# untitled.net
KiCad netlist of a schematic drawn in EAGLE
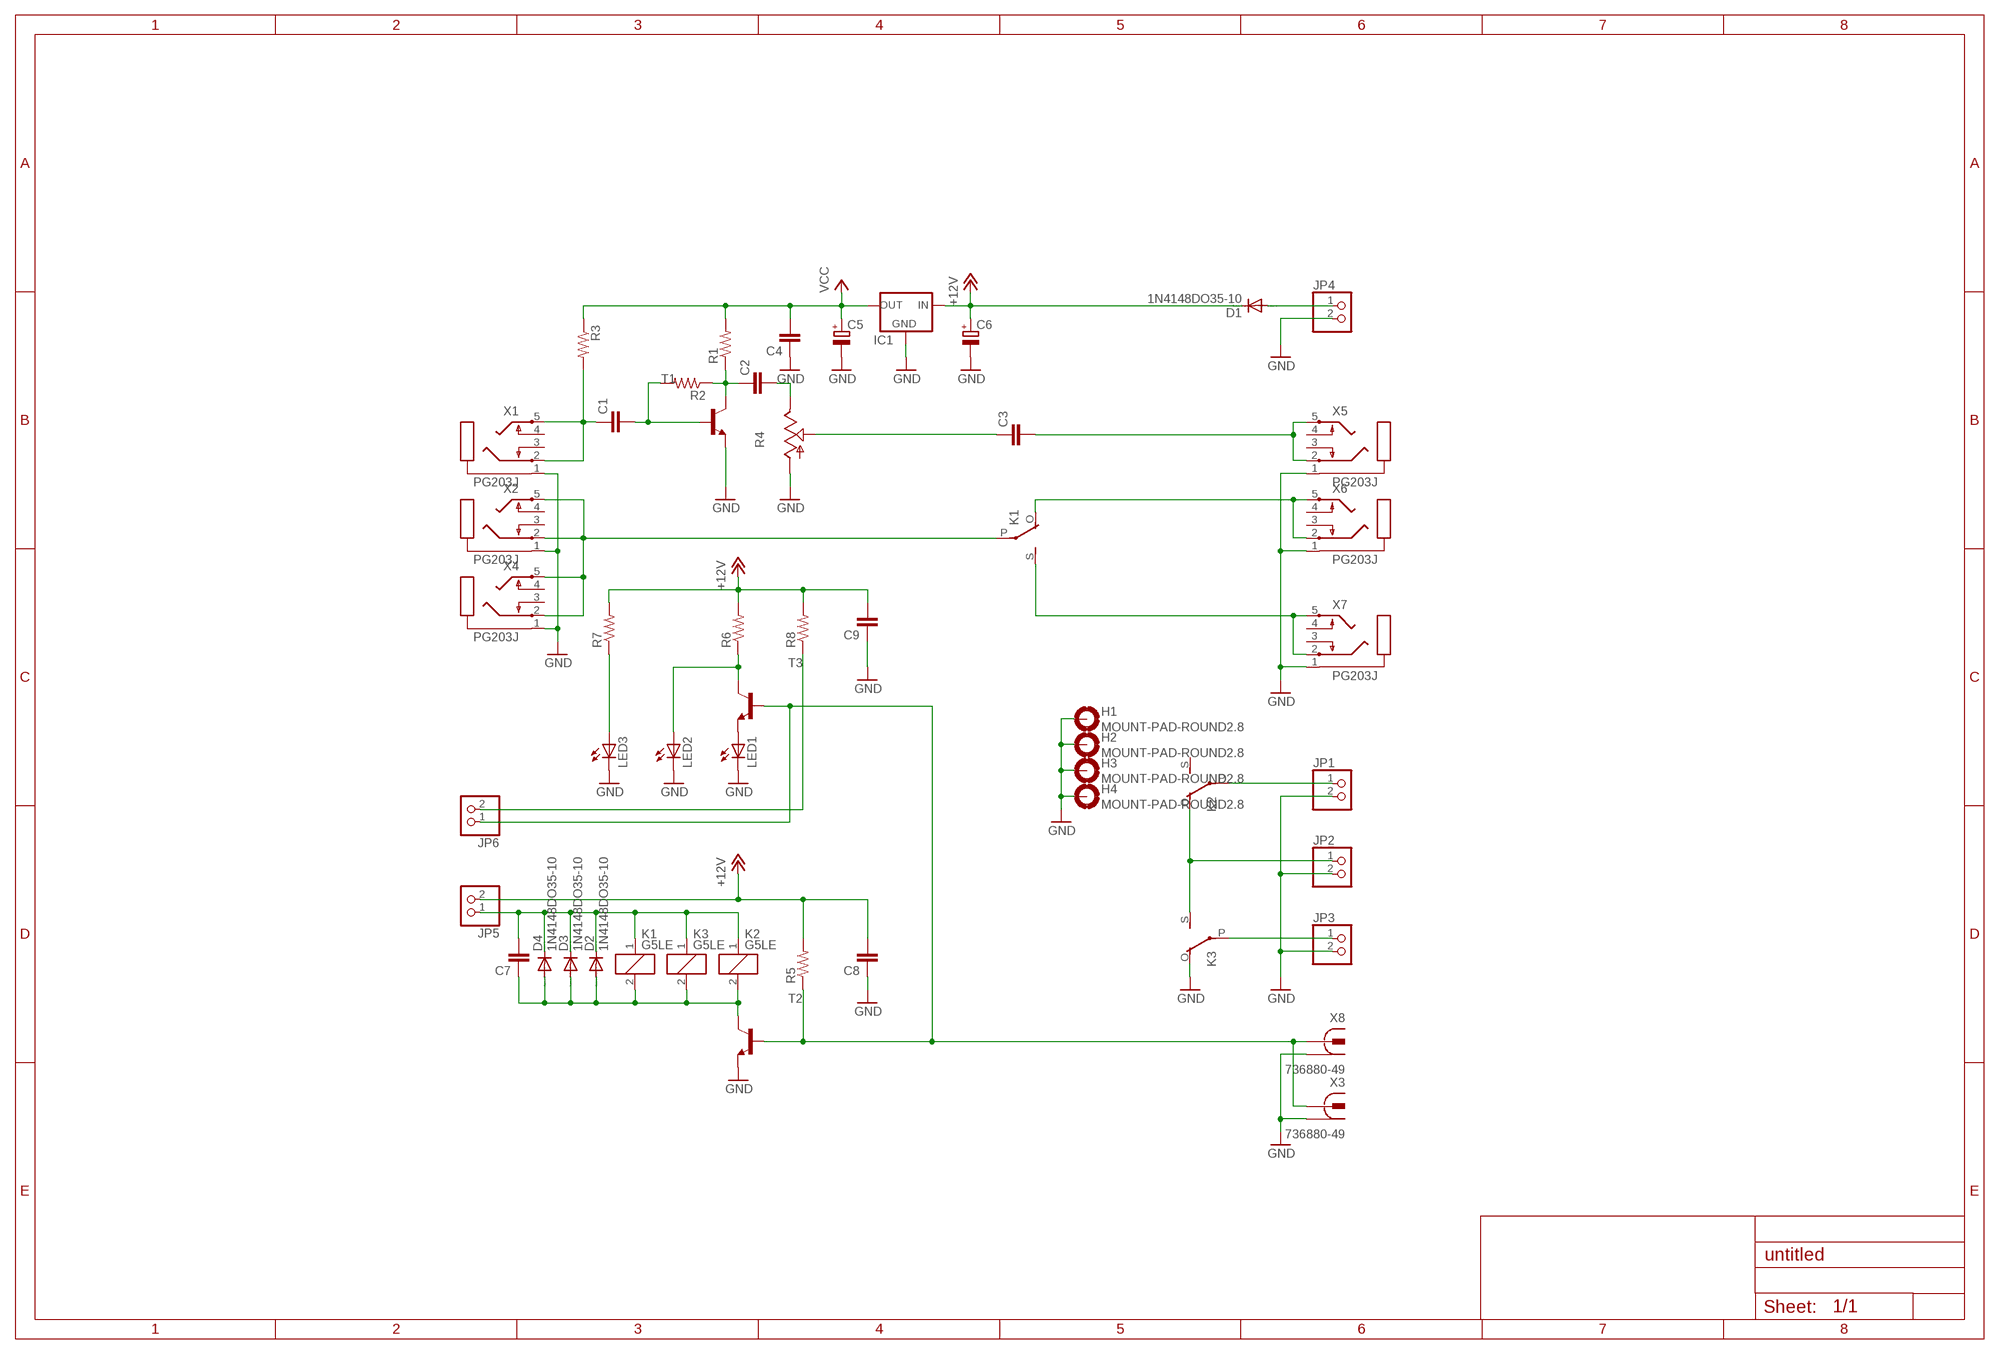
[diagram p0: schematic, sheet 1]

(export (version "E")
  (design (tool "Eeschema 10.0.6"))
  (components
    (comp (ref "C1")
      (value "C-EU050-025X075")
      (footprint "eagle-import:C050-025X075")
      (libsource (lib "eagle-import") (part "C-EU050-025X075"))
    )
    (comp (ref "C2")
      (value "C-EU050-025X075")
      (footprint "eagle-import:C050-025X075")
      (libsource (lib "eagle-import") (part "C-EU050-025X075"))
    )
    (comp (ref "C3")
      (value "C-EU050-025X075")
      (footprint "eagle-import:C050-025X075")
      (libsource (lib "eagle-import") (part "C-EU050-025X075"))
    )
    (comp (ref "C4")
      (value "C-EU050-025X075")
      (footprint "eagle-import:C050-025X075")
      (libsource (lib "eagle-import") (part "C-EU050-025X075"))
    )
    (comp (ref "C5")
      (value "CPOL-EUE2.5-6")
      (footprint "eagle-import:E2,5-6")
      (libsource (lib "eagle-import") (part "CPOL-EUE2.5-6"))
    )
    (comp (ref "C6")
      (value "CPOL-EUE2.5-6")
      (footprint "eagle-import:E2,5-6")
      (libsource (lib "eagle-import") (part "CPOL-EUE2.5-6"))
    )
    (comp (ref "C7")
      (value "C-EU050-025X075")
      (footprint "eagle-import:C050-025X075")
      (libsource (lib "eagle-import") (part "C-EU050-025X075"))
    )
    (comp (ref "C8")
      (value "C-EU050-025X075")
      (footprint "eagle-import:C050-025X075")
      (libsource (lib "eagle-import") (part "C-EU050-025X075"))
    )
    (comp (ref "C9")
      (value "C-EU050-025X075")
      (footprint "eagle-import:C050-025X075")
      (libsource (lib "eagle-import") (part "C-EU050-025X075"))
    )
    (comp (ref "D1")
      (value "1N4148DO35-10")
      (footprint "eagle-import:DO35-10")
      (libsource (lib "eagle-import") (part "1N4148DO35-10"))
    )
    (comp (ref "D2")
      (value "1N4148DO35-10")
      (footprint "eagle-import:DO35-10")
      (libsource (lib "eagle-import") (part "1N4148DO35-10"))
    )
    (comp (ref "D3")
      (value "1N4148DO35-10")
      (footprint "eagle-import:DO35-10")
      (libsource (lib "eagle-import") (part "1N4148DO35-10"))
    )
    (comp (ref "D4")
      (value "1N4148DO35-10")
      (footprint "eagle-import:DO35-10")
      (libsource (lib "eagle-import") (part "1N4148DO35-10"))
    )
    (comp (ref "H1")
      (value "MOUNT-PAD-ROUND2.8")
      (footprint "eagle-import:2,8-PAD")
      (libsource (lib "eagle-import") (part "MOUNT-PAD-ROUND2.8"))
    )
    (comp (ref "H2")
      (value "MOUNT-PAD-ROUND2.8")
      (footprint "eagle-import:2,8-PAD")
      (libsource (lib "eagle-import") (part "MOUNT-PAD-ROUND2.8"))
    )
    (comp (ref "H3")
      (value "MOUNT-PAD-ROUND2.8")
      (footprint "eagle-import:2,8-PAD")
      (libsource (lib "eagle-import") (part "MOUNT-PAD-ROUND2.8"))
    )
    (comp (ref "H4")
      (value "MOUNT-PAD-ROUND2.8")
      (footprint "eagle-import:2,8-PAD")
      (libsource (lib "eagle-import") (part "MOUNT-PAD-ROUND2.8"))
    )
    (comp (ref "IC1")
      (value "78XXS")
      (footprint "eagle-import:78XXS")
      (libsource (lib "eagle-import") (part "78XXS"))
    )
    (comp (ref "JP1")
      (value "PINHD-1X2")
      (footprint "eagle-import:1X02")
      (libsource (lib "eagle-import") (part "PINHD-1X2"))
    )
    (comp (ref "JP2")
      (value "PINHD-1X2")
      (footprint "eagle-import:1X02")
      (libsource (lib "eagle-import") (part "PINHD-1X2"))
    )
    (comp (ref "JP3")
      (value "PINHD-1X2")
      (footprint "eagle-import:1X02")
      (libsource (lib "eagle-import") (part "PINHD-1X2"))
    )
    (comp (ref "JP4")
      (value "PINHD-1X2")
      (footprint "eagle-import:1X02")
      (libsource (lib "eagle-import") (part "PINHD-1X2"))
    )
    (comp (ref "JP5")
      (value "PINHD-1X2")
      (footprint "eagle-import:1X02")
      (libsource (lib "eagle-import") (part "PINHD-1X2"))
    )
    (comp (ref "JP6")
      (value "PINHD-1X2")
      (footprint "eagle-import:1X02")
      (libsource (lib "eagle-import") (part "PINHD-1X2"))
    )
    (comp (ref "K1")
      (value "G5LE")
      (footprint "eagle-import:G5LE")
      (libsource (lib "eagle-import") (part "G5LE"))
    )
    (comp (ref "K2")
      (value "G5LE")
      (footprint "eagle-import:G5LE")
      (libsource (lib "eagle-import") (part "G5LE"))
    )
    (comp (ref "K3")
      (value "G5LE")
      (footprint "eagle-import:G5LE")
      (libsource (lib "eagle-import") (part "G5LE"))
    )
    (comp (ref "LED1")
      (value "LED3MM")
      (footprint "eagle-import:LED3MM")
      (libsource (lib "eagle-import") (part "LED3MM"))
    )
    (comp (ref "LED2")
      (value "LED3MM")
      (footprint "eagle-import:LED3MM")
      (libsource (lib "eagle-import") (part "LED3MM"))
    )
    (comp (ref "LED3")
      (value "LED3MM")
      (footprint "eagle-import:LED3MM")
      (libsource (lib "eagle-import") (part "LED3MM"))
    )
    (comp (ref "R1")
      (value "R-US_0207/7")
      (footprint "eagle-import:0207_7")
      (libsource (lib "eagle-import") (part "R-US_0207/7"))
    )
    (comp (ref "R2")
      (value "R-US_0207/7")
      (footprint "eagle-import:0207_7")
      (libsource (lib "eagle-import") (part "R-US_0207/7"))
    )
    (comp (ref "R3")
      (value "R-US_0207/7")
      (footprint "eagle-import:0207_7")
      (libsource (lib "eagle-import") (part "R-US_0207/7"))
    )
    (comp (ref "R4")
      (value "TRIM_US-CIP20C-6MM")
      (footprint "eagle-import:CIP20C-6MM")
      (libsource (lib "eagle-import") (part "TRIM_US-CIP20C-6MM"))
    )
    (comp (ref "R5")
      (value "R-US_0207/7")
      (footprint "eagle-import:0207_7")
      (libsource (lib "eagle-import") (part "R-US_0207/7"))
    )
    (comp (ref "R6")
      (value "R-US_0207/7")
      (footprint "eagle-import:0207_7")
      (libsource (lib "eagle-import") (part "R-US_0207/7"))
    )
    (comp (ref "R7")
      (value "R-US_0207/7")
      (footprint "eagle-import:0207_7")
      (libsource (lib "eagle-import") (part "R-US_0207/7"))
    )
    (comp (ref "R8")
      (value "R-US_0207/7")
      (footprint "eagle-import:0207_7")
      (libsource (lib "eagle-import") (part "R-US_0207/7"))
    )
    (comp (ref "T1")
      (value "-NPN-TO92-EBC")
      (footprint "eagle-import:TO92-EBC")
      (libsource (lib "eagle-import") (part "-NPN-TO92-EBC"))
    )
    (comp (ref "T2")
      (value "-NPN-TO92-EBC")
      (footprint "eagle-import:TO92-EBC")
      (libsource (lib "eagle-import") (part "-NPN-TO92-EBC"))
    )
    (comp (ref "T3")
      (value "-NPN-TO92-EBC")
      (footprint "eagle-import:TO92-EBC")
      (libsource (lib "eagle-import") (part "-NPN-TO92-EBC"))
    )
    (comp (ref "X1")
      (value "PG203J")
      (footprint "eagle-import:PG203J")
      (libsource (lib "eagle-import") (part "PG203J"))
    )
    (comp (ref "X2")
      (value "PG203J")
      (footprint "eagle-import:PG203J")
      (libsource (lib "eagle-import") (part "PG203J"))
    )
    (comp (ref "X3")
      (value "736880-49")
      (footprint "eagle-import:736880-49")
      (libsource (lib "eagle-import") (part "736880-49"))
    )
    (comp (ref "X4")
      (value "PG203J")
      (footprint "eagle-import:PG203J")
      (libsource (lib "eagle-import") (part "PG203J"))
    )
    (comp (ref "X5")
      (value "PG203J")
      (footprint "eagle-import:PG203J")
      (libsource (lib "eagle-import") (part "PG203J"))
    )
    (comp (ref "X6")
      (value "PG203J")
      (footprint "eagle-import:PG203J")
      (libsource (lib "eagle-import") (part "PG203J"))
    )
    (comp (ref "X7")
      (value "PG203J")
      (footprint "eagle-import:PG203J")
      (libsource (lib "eagle-import") (part "PG203J"))
    )
    (comp (ref "X8")
      (value "736880-49")
      (footprint "eagle-import:736880-49")
      (libsource (lib "eagle-import") (part "736880-49"))
    )
  )
  (nets
    (net (code "1") (name "+12V") (class "Default")
      (node (ref "C6") (pin "+") (pinfunction "+_+") (pintype "passive"))
      (node (ref "C8") (pin "2") (pinfunction "2_2") (pintype "passive"))
      (node (ref "C9") (pin "2") (pinfunction "2_2") (pintype "passive"))
      (node (ref "D1") (pin "C") (pinfunction "C_C") (pintype "passive"))
      (node (ref "IC1") (pin "IN") (pinfunction "IN_IN") (pintype "input"))
      (node (ref "JP5") (pin "2") (pinfunction "2_2") (pintype "passive"))
      (node (ref "R5") (pin "2") (pinfunction "2_2") (pintype "passive"))
      (node (ref "R6") (pin "2") (pinfunction "2_2") (pintype "passive"))
      (node (ref "R7") (pin "2") (pinfunction "2_2") (pintype "passive"))
      (node (ref "R8") (pin "2") (pinfunction "2_2") (pintype "passive"))
    )
    (net (code "2") (name "GND") (class "Default")
      (node (ref "C4") (pin "1") (pinfunction "1_1") (pintype "passive"))
      (node (ref "C5") (pin "-") (pinfunction "-_-") (pintype "passive"))
      (node (ref "C6") (pin "-") (pinfunction "-_-") (pintype "passive"))
      (node (ref "C8") (pin "1") (pinfunction "1_1") (pintype "passive"))
      (node (ref "C9") (pin "1") (pinfunction "1_1") (pintype "passive"))
      (node (ref "H1") (pin "B2,8") (pinfunction "MOUNT_B2,8") (pintype "passive"))
      (node (ref "H2") (pin "B2,8") (pinfunction "MOUNT_B2,8") (pintype "passive"))
      (node (ref "H3") (pin "B2,8") (pinfunction "MOUNT_B2,8") (pintype "passive"))
      (node (ref "H4") (pin "B2,8") (pinfunction "MOUNT_B2,8") (pintype "passive"))
      (node (ref "IC1") (pin "GND") (pinfunction "GND_GND") (pintype "input"))
      (node (ref "JP1") (pin "2") (pinfunction "2_2") (pintype "passive"))
      (node (ref "JP2") (pin "2") (pinfunction "2_2") (pintype "passive"))
      (node (ref "JP3") (pin "2") (pinfunction "2_2") (pintype "passive"))
      (node (ref "JP4") (pin "2") (pinfunction "2_2") (pintype "passive"))
      (node (ref "K3") (pin "O") (pinfunction "O_O") (pintype "passive"))
      (node (ref "LED1") (pin "K") (pinfunction "C_K") (pintype "passive"))
      (node (ref "LED2") (pin "K") (pinfunction "C_K") (pintype "passive"))
      (node (ref "LED3") (pin "K") (pinfunction "C_K") (pintype "passive"))
      (node (ref "R4") (pin "A") (pinfunction "A_A") (pintype "passive"))
      (node (ref "T1") (pin "E") (pinfunction "E_E") (pintype "passive"))
      (node (ref "T2") (pin "E") (pinfunction "E_E") (pintype "passive"))
      (node (ref "X1") (pin "1") (pinfunction "1_1") (pintype "passive"))
      (node (ref "X2") (pin "1") (pinfunction "1_1") (pintype "passive"))
      (node (ref "X3") (pin "1") (pinfunction "1_1") (pintype "passive"))
      (node (ref "X3") (pin "1@1") (pinfunction "1_1@1") (pintype "passive"))
      (node (ref "X3") (pin "1@2") (pinfunction "1_1@2") (pintype "passive"))
      (node (ref "X4") (pin "1") (pinfunction "1_1") (pintype "passive"))
      (node (ref "X5") (pin "1") (pinfunction "1_1") (pintype "passive"))
      (node (ref "X6") (pin "1") (pinfunction "1_1") (pintype "passive"))
      (node (ref "X7") (pin "1") (pinfunction "1_1") (pintype "passive"))
      (node (ref "X8") (pin "1") (pinfunction "1_1") (pintype "passive"))
      (node (ref "X8") (pin "1@1") (pinfunction "1_1@1") (pintype "passive"))
      (node (ref "X8") (pin "1@2") (pinfunction "1_1@2") (pintype "passive"))
    )
    (net (code "3") (name "Net-(C1-Pad1)") (class "Default")
      (node (ref "C1") (pin "1") (pinfunction "1_1") (pintype "passive"))
      (node (ref "R3") (pin "2") (pinfunction "2_2") (pintype "passive"))
      (node (ref "X1") (pin "2") (pinfunction "2_2") (pintype "passive"))
      (node (ref "X1") (pin "5") (pinfunction "5_5") (pintype "passive"))
    )
    (net (code "4") (name "Net-(C1-Pad2)") (class "Default")
      (node (ref "C1") (pin "2") (pinfunction "2_2") (pintype "passive"))
      (node (ref "R2") (pin "2") (pinfunction "2_2") (pintype "passive"))
      (node (ref "T1") (pin "B") (pinfunction "B_B") (pintype "passive"))
    )
    (net (code "5") (name "Net-(C2-Pad1)") (class "Default")
      (node (ref "C2") (pin "1") (pinfunction "1_1") (pintype "passive"))
      (node (ref "R1") (pin "1") (pinfunction "1_1") (pintype "passive"))
      (node (ref "R2") (pin "1") (pinfunction "1_1") (pintype "passive"))
      (node (ref "T1") (pin "C") (pinfunction "C_C") (pintype "passive"))
    )
    (net (code "6") (name "Net-(C2-Pad2)") (class "Default")
      (node (ref "C2") (pin "2") (pinfunction "2_2") (pintype "passive"))
      (node (ref "R4") (pin "E") (pinfunction "E_E") (pintype "passive"))
    )
    (net (code "7") (name "Net-(C3-Pad1)") (class "Default")
      (node (ref "C3") (pin "1") (pinfunction "1_1") (pintype "passive"))
      (node (ref "R4") (pin "S") (pinfunction "S_S") (pintype "passive"))
    )
    (net (code "8") (name "Net-(C3-Pad2)") (class "Default")
      (node (ref "C3") (pin "2") (pinfunction "2_2") (pintype "passive"))
      (node (ref "X5") (pin "2") (pinfunction "2_2") (pintype "passive"))
      (node (ref "X5") (pin "5") (pinfunction "5_5") (pintype "passive"))
    )
    (net (code "9") (name "Net-(C7-Pad1)") (class "Default")
      (node (ref "C7") (pin "1") (pinfunction "1_1") (pintype "passive"))
      (node (ref "D2") (pin "A") (pinfunction "A_A") (pintype "passive"))
      (node (ref "D3") (pin "A") (pinfunction "A_A") (pintype "passive"))
      (node (ref "D4") (pin "A") (pinfunction "A_A") (pintype "passive"))
      (node (ref "K1") (pin "2") (pinfunction "2_2") (pintype "passive"))
      (node (ref "K2") (pin "2") (pinfunction "2_2") (pintype "passive"))
      (node (ref "K3") (pin "2") (pinfunction "2_2") (pintype "passive"))
      (node (ref "T2") (pin "C") (pinfunction "C_C") (pintype "passive"))
    )
    (net (code "10") (name "Net-(C7-Pad2)") (class "Default")
      (node (ref "C7") (pin "2") (pinfunction "2_2") (pintype "passive"))
      (node (ref "D2") (pin "C") (pinfunction "C_C") (pintype "passive"))
      (node (ref "D3") (pin "C") (pinfunction "C_C") (pintype "passive"))
      (node (ref "D4") (pin "C") (pinfunction "C_C") (pintype "passive"))
      (node (ref "JP5") (pin "1") (pinfunction "1_1") (pintype "passive"))
      (node (ref "K1") (pin "1") (pinfunction "1_1") (pintype "passive"))
      (node (ref "K2") (pin "1") (pinfunction "1_1") (pintype "passive"))
      (node (ref "K3") (pin "1") (pinfunction "1_1") (pintype "passive"))
    )
    (net (code "11") (name "Net-(D1-PadA)") (class "Default")
      (node (ref "D1") (pin "A") (pinfunction "A_A") (pintype "passive"))
      (node (ref "JP4") (pin "1") (pinfunction "1_1") (pintype "passive"))
    )
    (net (code "12") (name "Net-(JP1-Pad1)") (class "Default")
      (node (ref "JP1") (pin "1") (pinfunction "1_1") (pintype "passive"))
      (node (ref "K2") (pin "P") (pinfunction "P_P") (pintype "passive"))
    )
    (net (code "13") (name "Net-(JP2-Pad1)") (class "Default")
      (node (ref "JP2") (pin "1") (pinfunction "1_1") (pintype "passive"))
      (node (ref "K2") (pin "O") (pinfunction "O_O") (pintype "passive"))
      (node (ref "K3") (pin "S") (pinfunction "S_S") (pintype "passive"))
    )
    (net (code "14") (name "Net-(JP3-Pad1)") (class "Default")
      (node (ref "JP3") (pin "1") (pinfunction "1_1") (pintype "passive"))
      (node (ref "K3") (pin "P") (pinfunction "P_P") (pintype "passive"))
    )
    (net (code "15") (name "Net-(JP6-Pad1)") (class "Default")
      (node (ref "JP6") (pin "1") (pinfunction "1_1") (pintype "passive"))
      (node (ref "R5") (pin "1") (pinfunction "1_1") (pintype "passive"))
      (node (ref "T2") (pin "B") (pinfunction "B_B") (pintype "passive"))
      (node (ref "T3") (pin "B") (pinfunction "B_B") (pintype "passive"))
      (node (ref "X3") (pin "2") (pinfunction "2_2") (pintype "passive"))
      (node (ref "X8") (pin "2") (pinfunction "2_2") (pintype "passive"))
    )
    (net (code "16") (name "Net-(JP6-Pad2)") (class "Default")
      (node (ref "JP6") (pin "2") (pinfunction "2_2") (pintype "passive"))
      (node (ref "R8") (pin "1") (pinfunction "1_1") (pintype "passive"))
    )
    (net (code "17") (name "Net-(K1-PadO)") (class "Default")
      (node (ref "K1") (pin "O") (pinfunction "O_O") (pintype "passive"))
      (node (ref "X6") (pin "2") (pinfunction "2_2") (pintype "passive"))
      (node (ref "X6") (pin "5") (pinfunction "5_5") (pintype "passive"))
    )
    (net (code "18") (name "Net-(K1-PadP)") (class "Default")
      (node (ref "K1") (pin "P") (pinfunction "P_P") (pintype "passive"))
      (node (ref "X2") (pin "2") (pinfunction "2_2") (pintype "passive"))
      (node (ref "X2") (pin "5") (pinfunction "5_5") (pintype "passive"))
      (node (ref "X4") (pin "2") (pinfunction "2_2") (pintype "passive"))
      (node (ref "X4") (pin "5") (pinfunction "5_5") (pintype "passive"))
    )
    (net (code "19") (name "Net-(K1-PadS)") (class "Default")
      (node (ref "K1") (pin "S") (pinfunction "S_S") (pintype "passive"))
      (node (ref "X7") (pin "2") (pinfunction "2_2") (pintype "passive"))
      (node (ref "X7") (pin "5") (pinfunction "5_5") (pintype "passive"))
    )
    (net (code "20") (name "Net-(LED1-PadA)") (class "Default")
      (node (ref "LED1") (pin "A") (pinfunction "A_A") (pintype "passive"))
      (node (ref "T3") (pin "E") (pinfunction "E_E") (pintype "passive"))
    )
    (net (code "21") (name "Net-(LED2-PadA)") (class "Default")
      (node (ref "LED2") (pin "A") (pinfunction "A_A") (pintype "passive"))
      (node (ref "R6") (pin "1") (pinfunction "1_1") (pintype "passive"))
      (node (ref "T3") (pin "C") (pinfunction "C_C") (pintype "passive"))
    )
    (net (code "22") (name "Net-(LED3-PadA)") (class "Default")
      (node (ref "LED3") (pin "A") (pinfunction "A_A") (pintype "passive"))
      (node (ref "R7") (pin "1") (pinfunction "1_1") (pintype "passive"))
    )
    (net (code "23") (name "VCC") (class "Default")
      (node (ref "C4") (pin "2") (pinfunction "2_2") (pintype "passive"))
      (node (ref "C5") (pin "+") (pinfunction "+_+") (pintype "passive"))
      (node (ref "IC1") (pin "OUT") (pinfunction "OUT_OUT") (pintype "passive"))
      (node (ref "R1") (pin "2") (pinfunction "2_2") (pintype "passive"))
      (node (ref "R3") (pin "1") (pinfunction "1_1") (pintype "passive"))
    )
    (net (code "24") (name "unconnected-(K2-PadS)") (class "Default")
      (node (ref "K2") (pin "S") (pinfunction "S_S") (pintype "passive"))
    )
    (net (code "25") (name "unconnected-(X1-Pad3)") (class "Default")
      (node (ref "X1") (pin "3") (pinfunction "3_3") (pintype "passive"))
    )
    (net (code "26") (name "unconnected-(X1-Pad4)") (class "Default")
      (node (ref "X1") (pin "4") (pinfunction "4_4") (pintype "passive"))
    )
    (net (code "27") (name "unconnected-(X2-Pad3)") (class "Default")
      (node (ref "X2") (pin "3") (pinfunction "3_3") (pintype "passive"))
    )
    (net (code "28") (name "unconnected-(X2-Pad4)") (class "Default")
      (node (ref "X2") (pin "4") (pinfunction "4_4") (pintype "passive"))
    )
    (net (code "29") (name "unconnected-(X4-Pad3)") (class "Default")
      (node (ref "X4") (pin "3") (pinfunction "3_3") (pintype "passive"))
    )
    (net (code "30") (name "unconnected-(X4-Pad4)") (class "Default")
      (node (ref "X4") (pin "4") (pinfunction "4_4") (pintype "passive"))
    )
    (net (code "31") (name "unconnected-(X5-Pad3)") (class "Default")
      (node (ref "X5") (pin "3") (pinfunction "3_3") (pintype "passive"))
    )
    (net (code "32") (name "unconnected-(X5-Pad4)") (class "Default")
      (node (ref "X5") (pin "4") (pinfunction "4_4") (pintype "passive"))
    )
    (net (code "33") (name "unconnected-(X6-Pad3)") (class "Default")
      (node (ref "X6") (pin "3") (pinfunction "3_3") (pintype "passive"))
    )
    (net (code "34") (name "unconnected-(X6-Pad4)") (class "Default")
      (node (ref "X6") (pin "4") (pinfunction "4_4") (pintype "passive"))
    )
    (net (code "35") (name "unconnected-(X7-Pad3)") (class "Default")
      (node (ref "X7") (pin "3") (pinfunction "3_3") (pintype "passive"))
    )
    (net (code "36") (name "unconnected-(X7-Pad4)") (class "Default")
      (node (ref "X7") (pin "4") (pinfunction "4_4") (pintype "passive"))
    )
  )
)
